# Circuit_EasyEDA.net
KiCad netlist of a schematic drawn in EasyEDA
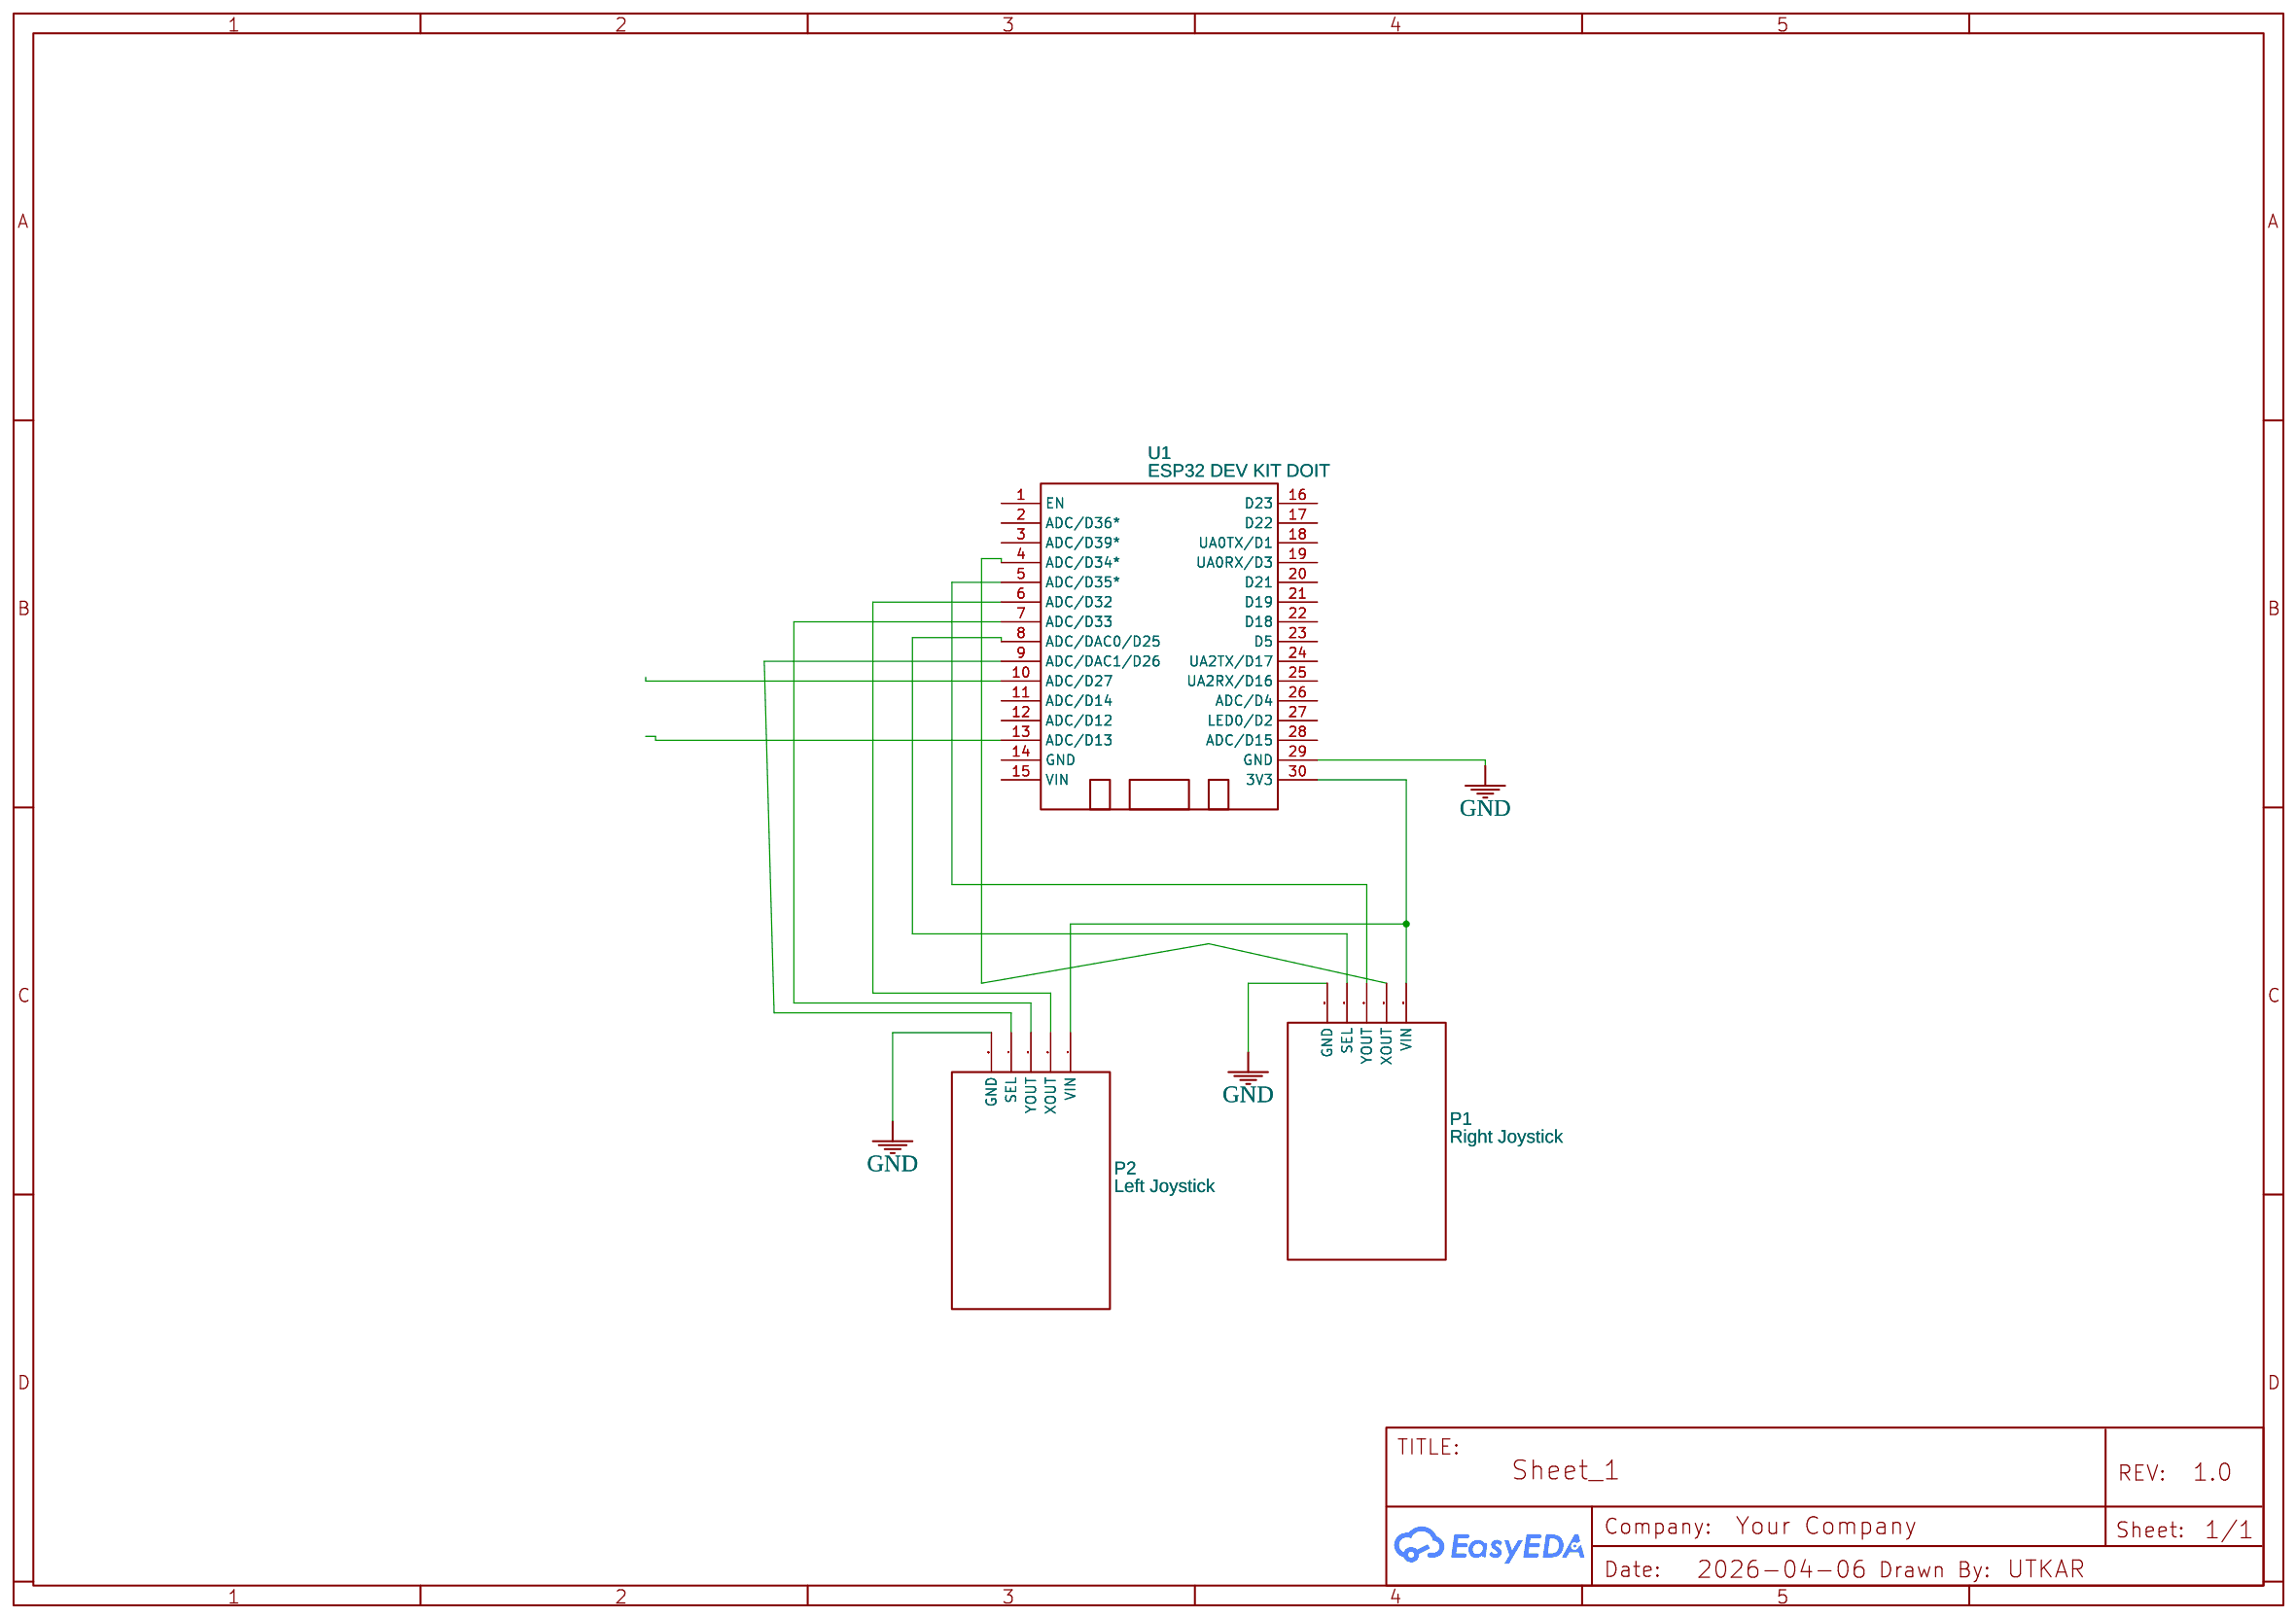
[diagram p0: schematic sheet]

(export (version "E")
  (design (tool "Eeschema 10.0.6"))
  (components
    (comp (ref "P1") (value "Right Joystick") (libsource (lib "") (part "JOYSTICK CPY")))
    (comp (ref "P2") (value "Left Joystick") (libsource (lib "") (part "JOYSTICK CPY")))
    (comp (ref "U1") (value "ESP32 DEV KIT DOIT") (libsource (lib "") (part "ESP32 DEV KIT DOIT")))
  )
  (nets
    (net (code "1") (name "GND") (class "Default")
      (node (ref "P1") (pin "GND") (pinfunction "GND_GND") (pintype "unspecified"))
      (node (ref "P2") (pin "GND") (pinfunction "GND_GND") (pintype "unspecified"))
      (node (ref "U1") (pin "29") (pinfunction "GND_29") (pintype "bidirectional"))
    )
    (net (code "2") (name "Net-(P1-SEL)") (class "Default")
      (node (ref "P1") (pin "Key") (pinfunction "SEL_Key") (pintype "unspecified"))
      (node (ref "U1") (pin "8") (pinfunction "ADC/DAC0/D25_8") (pintype "bidirectional"))
    )
    (net (code "3") (name "Net-(P1-VIN)") (class "Default")
      (node (ref "P1") (pin "VCC") (pinfunction "VIN_VCC") (pintype "unspecified"))
      (node (ref "P2") (pin "VCC") (pinfunction "VIN_VCC") (pintype "unspecified"))
      (node (ref "U1") (pin "30") (pinfunction "3V3_30") (pintype "bidirectional"))
    )
    (net (code "4") (name "Net-(P2-SEL)") (class "Default")
      (node (ref "P2") (pin "Key") (pinfunction "SEL_Key") (pintype "unspecified"))
      (node (ref "U1") (pin "9") (pinfunction "ADC/DAC1/D26_9") (pintype "bidirectional"))
    )
    (net (code "5") (name "Net-(U1-ADC{slash}D32)") (class "Default")
      (node (ref "P2") (pin "XOUT") (pinfunction "XOUT_XOUT") (pintype "unspecified"))
      (node (ref "U1") (pin "6") (pinfunction "ADC/D32_6") (pintype "bidirectional"))
    )
    (net (code "6") (name "Net-(U1-ADC{slash}D33)") (class "Default")
      (node (ref "P2") (pin "YOUT") (pinfunction "YOUT_YOUT") (pintype "unspecified"))
      (node (ref "U1") (pin "7") (pinfunction "ADC/D33_7") (pintype "bidirectional"))
    )
    (net (code "7") (name "Net-(U1-ADC{slash}D34*)") (class "Default")
      (node (ref "P1") (pin "XOUT") (pinfunction "XOUT_XOUT") (pintype "unspecified"))
      (node (ref "U1") (pin "4") (pinfunction "ADC/D34*_4") (pintype "input"))
    )
    (net (code "8") (name "Net-(U1-ADC{slash}D35*)") (class "Default")
      (node (ref "P1") (pin "YOUT") (pinfunction "YOUT_YOUT") (pintype "unspecified"))
      (node (ref "U1") (pin "5") (pinfunction "ADC/D35*_5") (pintype "input"))
    )
    (net (code "9") (name "unconnected-(U1-ADC{slash}D4-Pad26)") (class "Default")
      (node (ref "U1") (pin "26") (pinfunction "ADC/D4_26") (pintype "bidirectional"))
    )
    (net (code "10") (name "unconnected-(U1-ADC{slash}D12-Pad12)") (class "Default")
      (node (ref "U1") (pin "12") (pinfunction "ADC/D12_12") (pintype "bidirectional"))
    )
    (net (code "11") (name "unconnected-(U1-ADC{slash}D13-Pad13)") (class "Default")
      (node (ref "U1") (pin "13") (pinfunction "ADC/D13_13") (pintype "bidirectional"))
    )
    (net (code "12") (name "unconnected-(U1-ADC{slash}D14-Pad11)") (class "Default")
      (node (ref "U1") (pin "11") (pinfunction "ADC/D14_11") (pintype "bidirectional"))
    )
    (net (code "13") (name "unconnected-(U1-ADC{slash}D15-Pad28)") (class "Default")
      (node (ref "U1") (pin "28") (pinfunction "ADC/D15_28") (pintype "bidirectional"))
    )
    (net (code "14") (name "unconnected-(U1-ADC{slash}D27-Pad10)") (class "Default")
      (node (ref "U1") (pin "10") (pinfunction "ADC/D27_10") (pintype "bidirectional"))
    )
    (net (code "15") (name "unconnected-(U1-ADC{slash}D36*-Pad2)") (class "Default")
      (node (ref "U1") (pin "2") (pinfunction "ADC/D36*_2") (pintype "input"))
    )
    (net (code "16") (name "unconnected-(U1-ADC{slash}D39*-Pad3)") (class "Default")
      (node (ref "U1") (pin "3") (pinfunction "ADC/D39*_3") (pintype "input"))
    )
    (net (code "17") (name "unconnected-(U1-D5-Pad23)") (class "Default")
      (node (ref "U1") (pin "23") (pinfunction "D5_23") (pintype "bidirectional"))
    )
    (net (code "18") (name "unconnected-(U1-D18-Pad22)") (class "Default")
      (node (ref "U1") (pin "22") (pinfunction "D18_22") (pintype "bidirectional"))
    )
    (net (code "19") (name "unconnected-(U1-D19-Pad21)") (class "Default")
      (node (ref "U1") (pin "21") (pinfunction "D19_21") (pintype "bidirectional"))
    )
    (net (code "20") (name "unconnected-(U1-D21-Pad20)") (class "Default")
      (node (ref "U1") (pin "20") (pinfunction "D21_20") (pintype "bidirectional"))
    )
    (net (code "21") (name "unconnected-(U1-D22-Pad17)") (class "Default")
      (node (ref "U1") (pin "17") (pinfunction "D22_17") (pintype "bidirectional"))
    )
    (net (code "22") (name "unconnected-(U1-D23-Pad16)") (class "Default")
      (node (ref "U1") (pin "16") (pinfunction "D23_16") (pintype "bidirectional"))
    )
    (net (code "23") (name "unconnected-(U1-EN-Pad1)") (class "Default")
      (node (ref "U1") (pin "1") (pinfunction "EN_1") (pintype "bidirectional"))
    )
    (net (code "24") (name "unconnected-(U1-GND-Pad14)") (class "Default")
      (node (ref "U1") (pin "14") (pinfunction "GND_14") (pintype "bidirectional"))
    )
    (net (code "25") (name "unconnected-(U1-LED0{slash}D2-Pad27)") (class "Default")
      (node (ref "U1") (pin "27") (pinfunction "LED0/D2_27") (pintype "bidirectional"))
    )
    (net (code "26") (name "unconnected-(U1-UA0RX{slash}D3-Pad19)") (class "Default")
      (node (ref "U1") (pin "19") (pinfunction "UA0RX/D3_19") (pintype "bidirectional"))
    )
    (net (code "27") (name "unconnected-(U1-UA0TX{slash}D1-Pad18)") (class "Default")
      (node (ref "U1") (pin "18") (pinfunction "UA0TX/D1_18") (pintype "bidirectional"))
    )
    (net (code "28") (name "unconnected-(U1-UA2RX{slash}D16-Pad25)") (class "Default")
      (node (ref "U1") (pin "25") (pinfunction "UA2RX/D16_25") (pintype "bidirectional"))
    )
    (net (code "29") (name "unconnected-(U1-UA2TX{slash}D17-Pad24)") (class "Default")
      (node (ref "U1") (pin "24") (pinfunction "UA2TX/D17_24") (pintype "bidirectional"))
    )
    (net (code "30") (name "unconnected-(U1-VIN-Pad15)") (class "Default")
      (node (ref "U1") (pin "15") (pinfunction "VIN_15") (pintype "input"))
    )
  )
)
